# ProProject_PowerDistribution_1_1.net
KiCad netlist of a schematic drawn in EasyEDA Pro
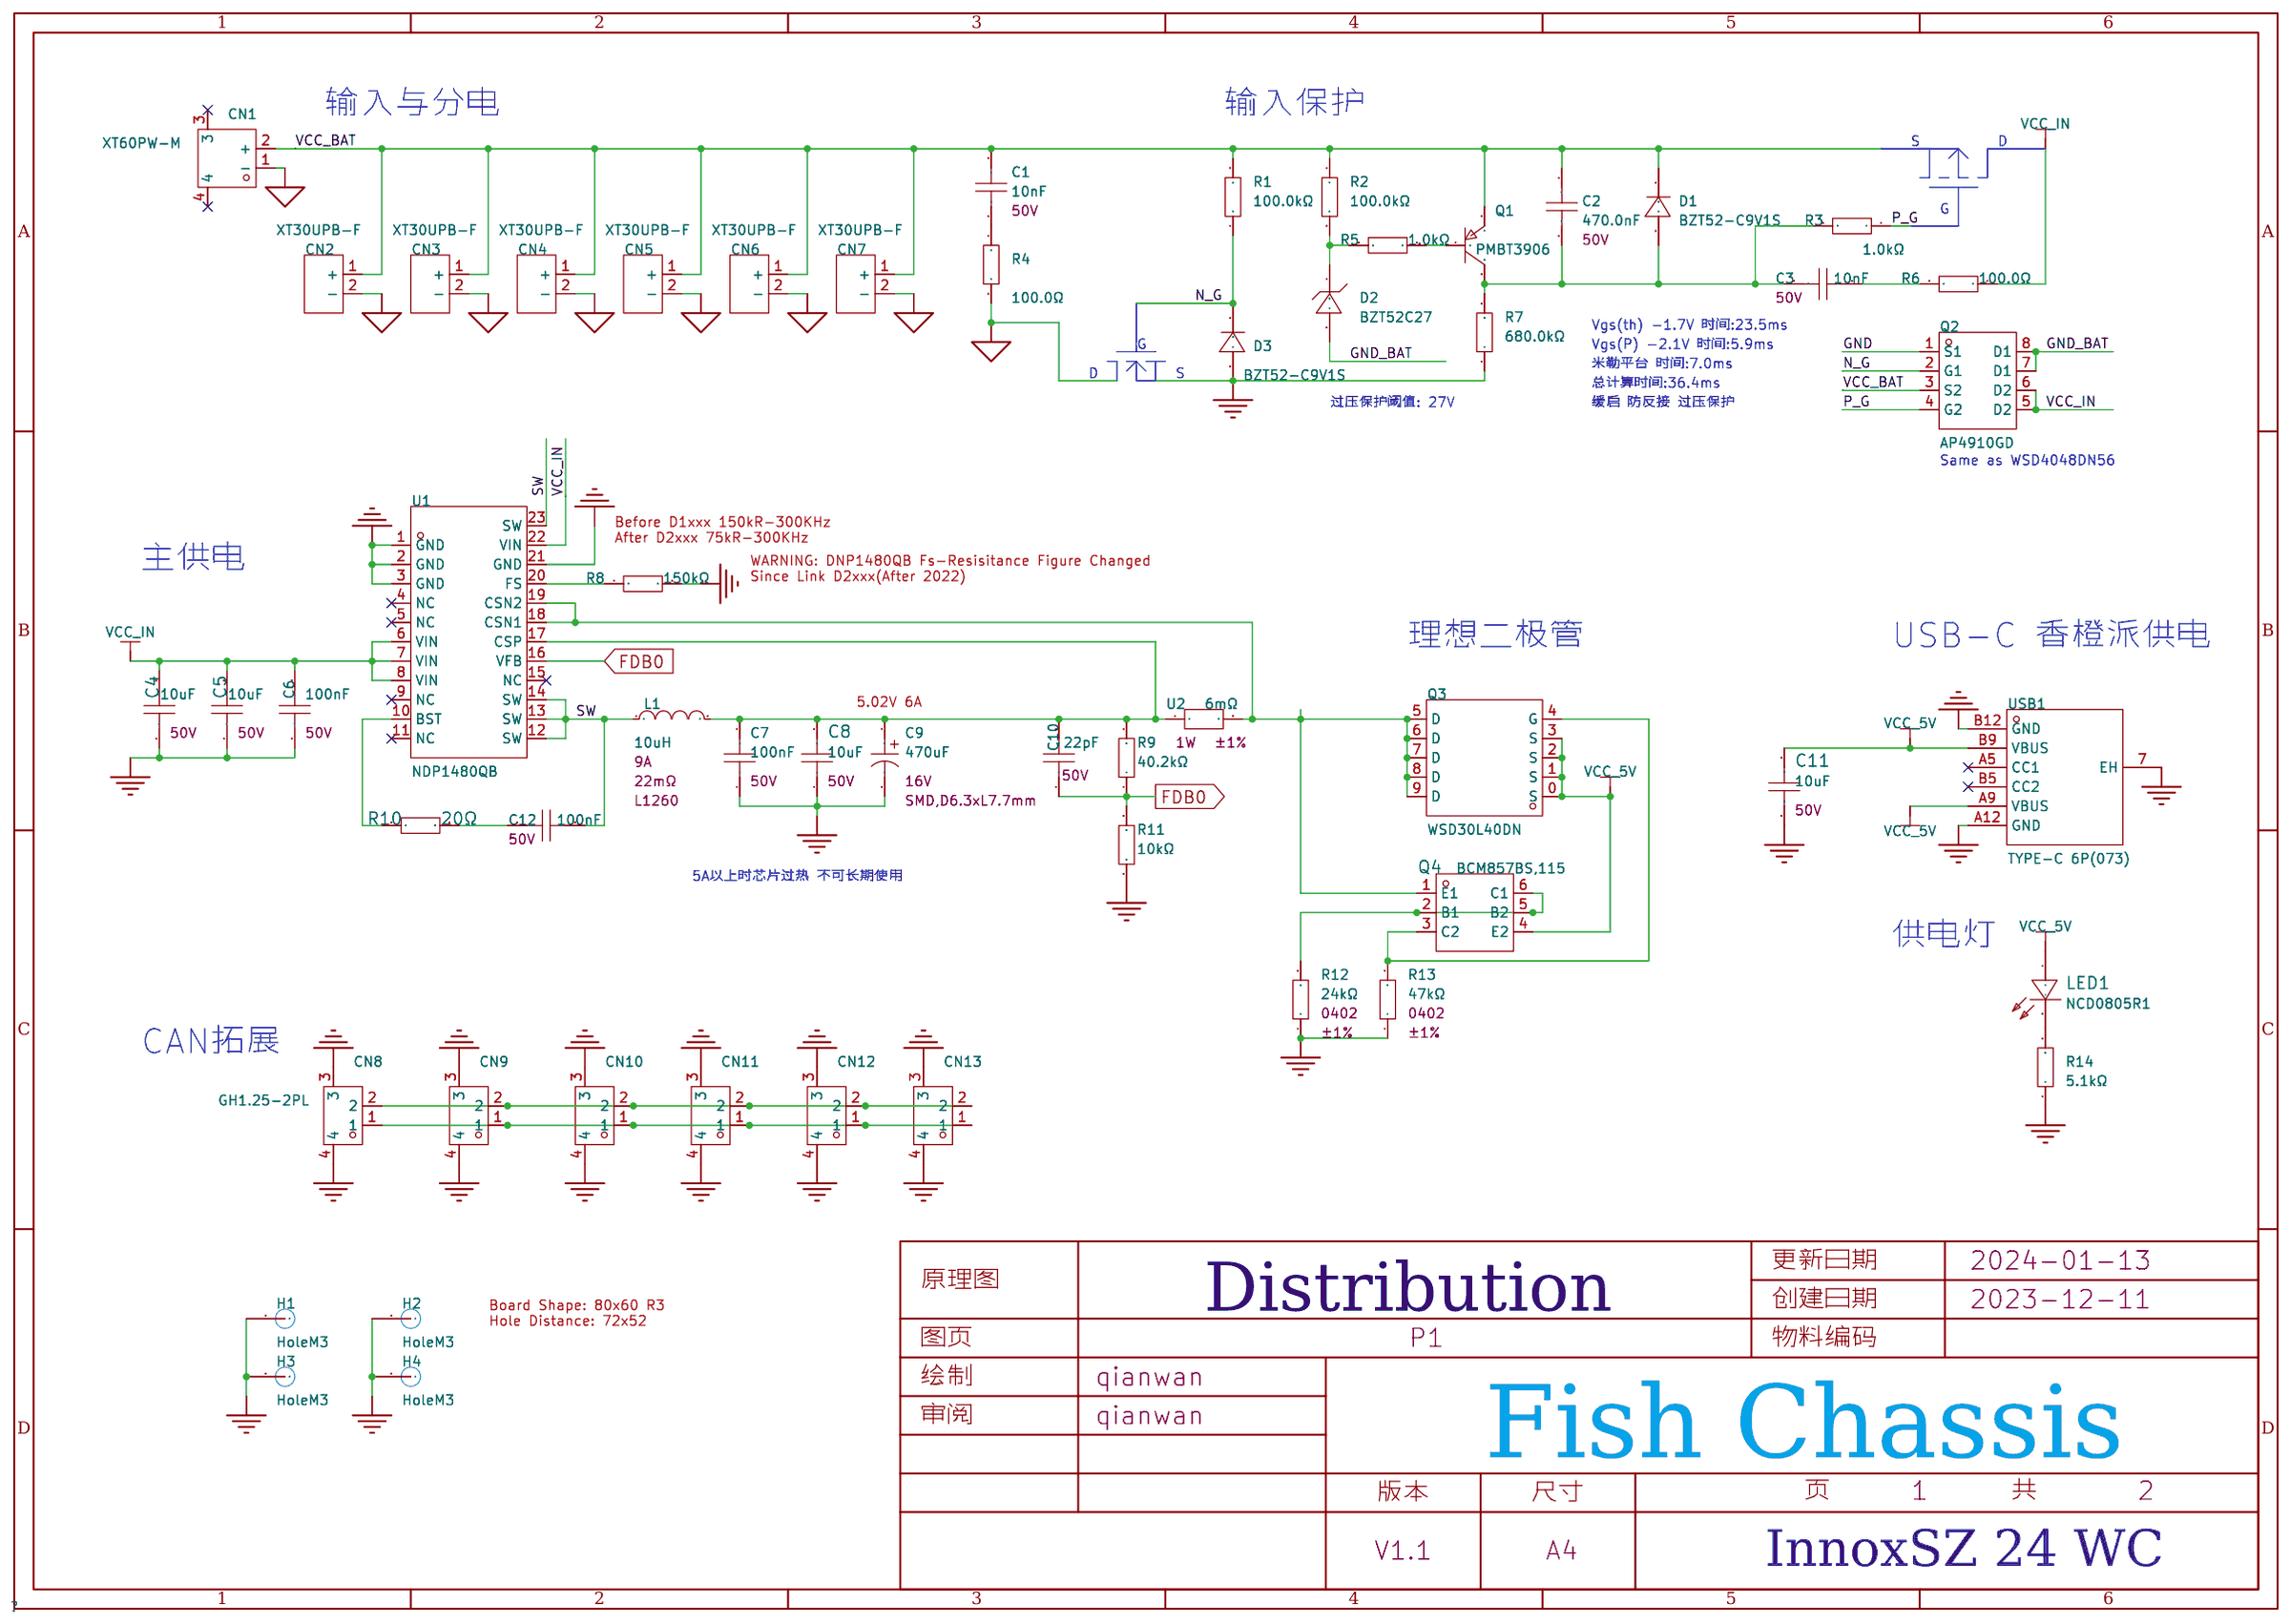
[diagram p0: P1]
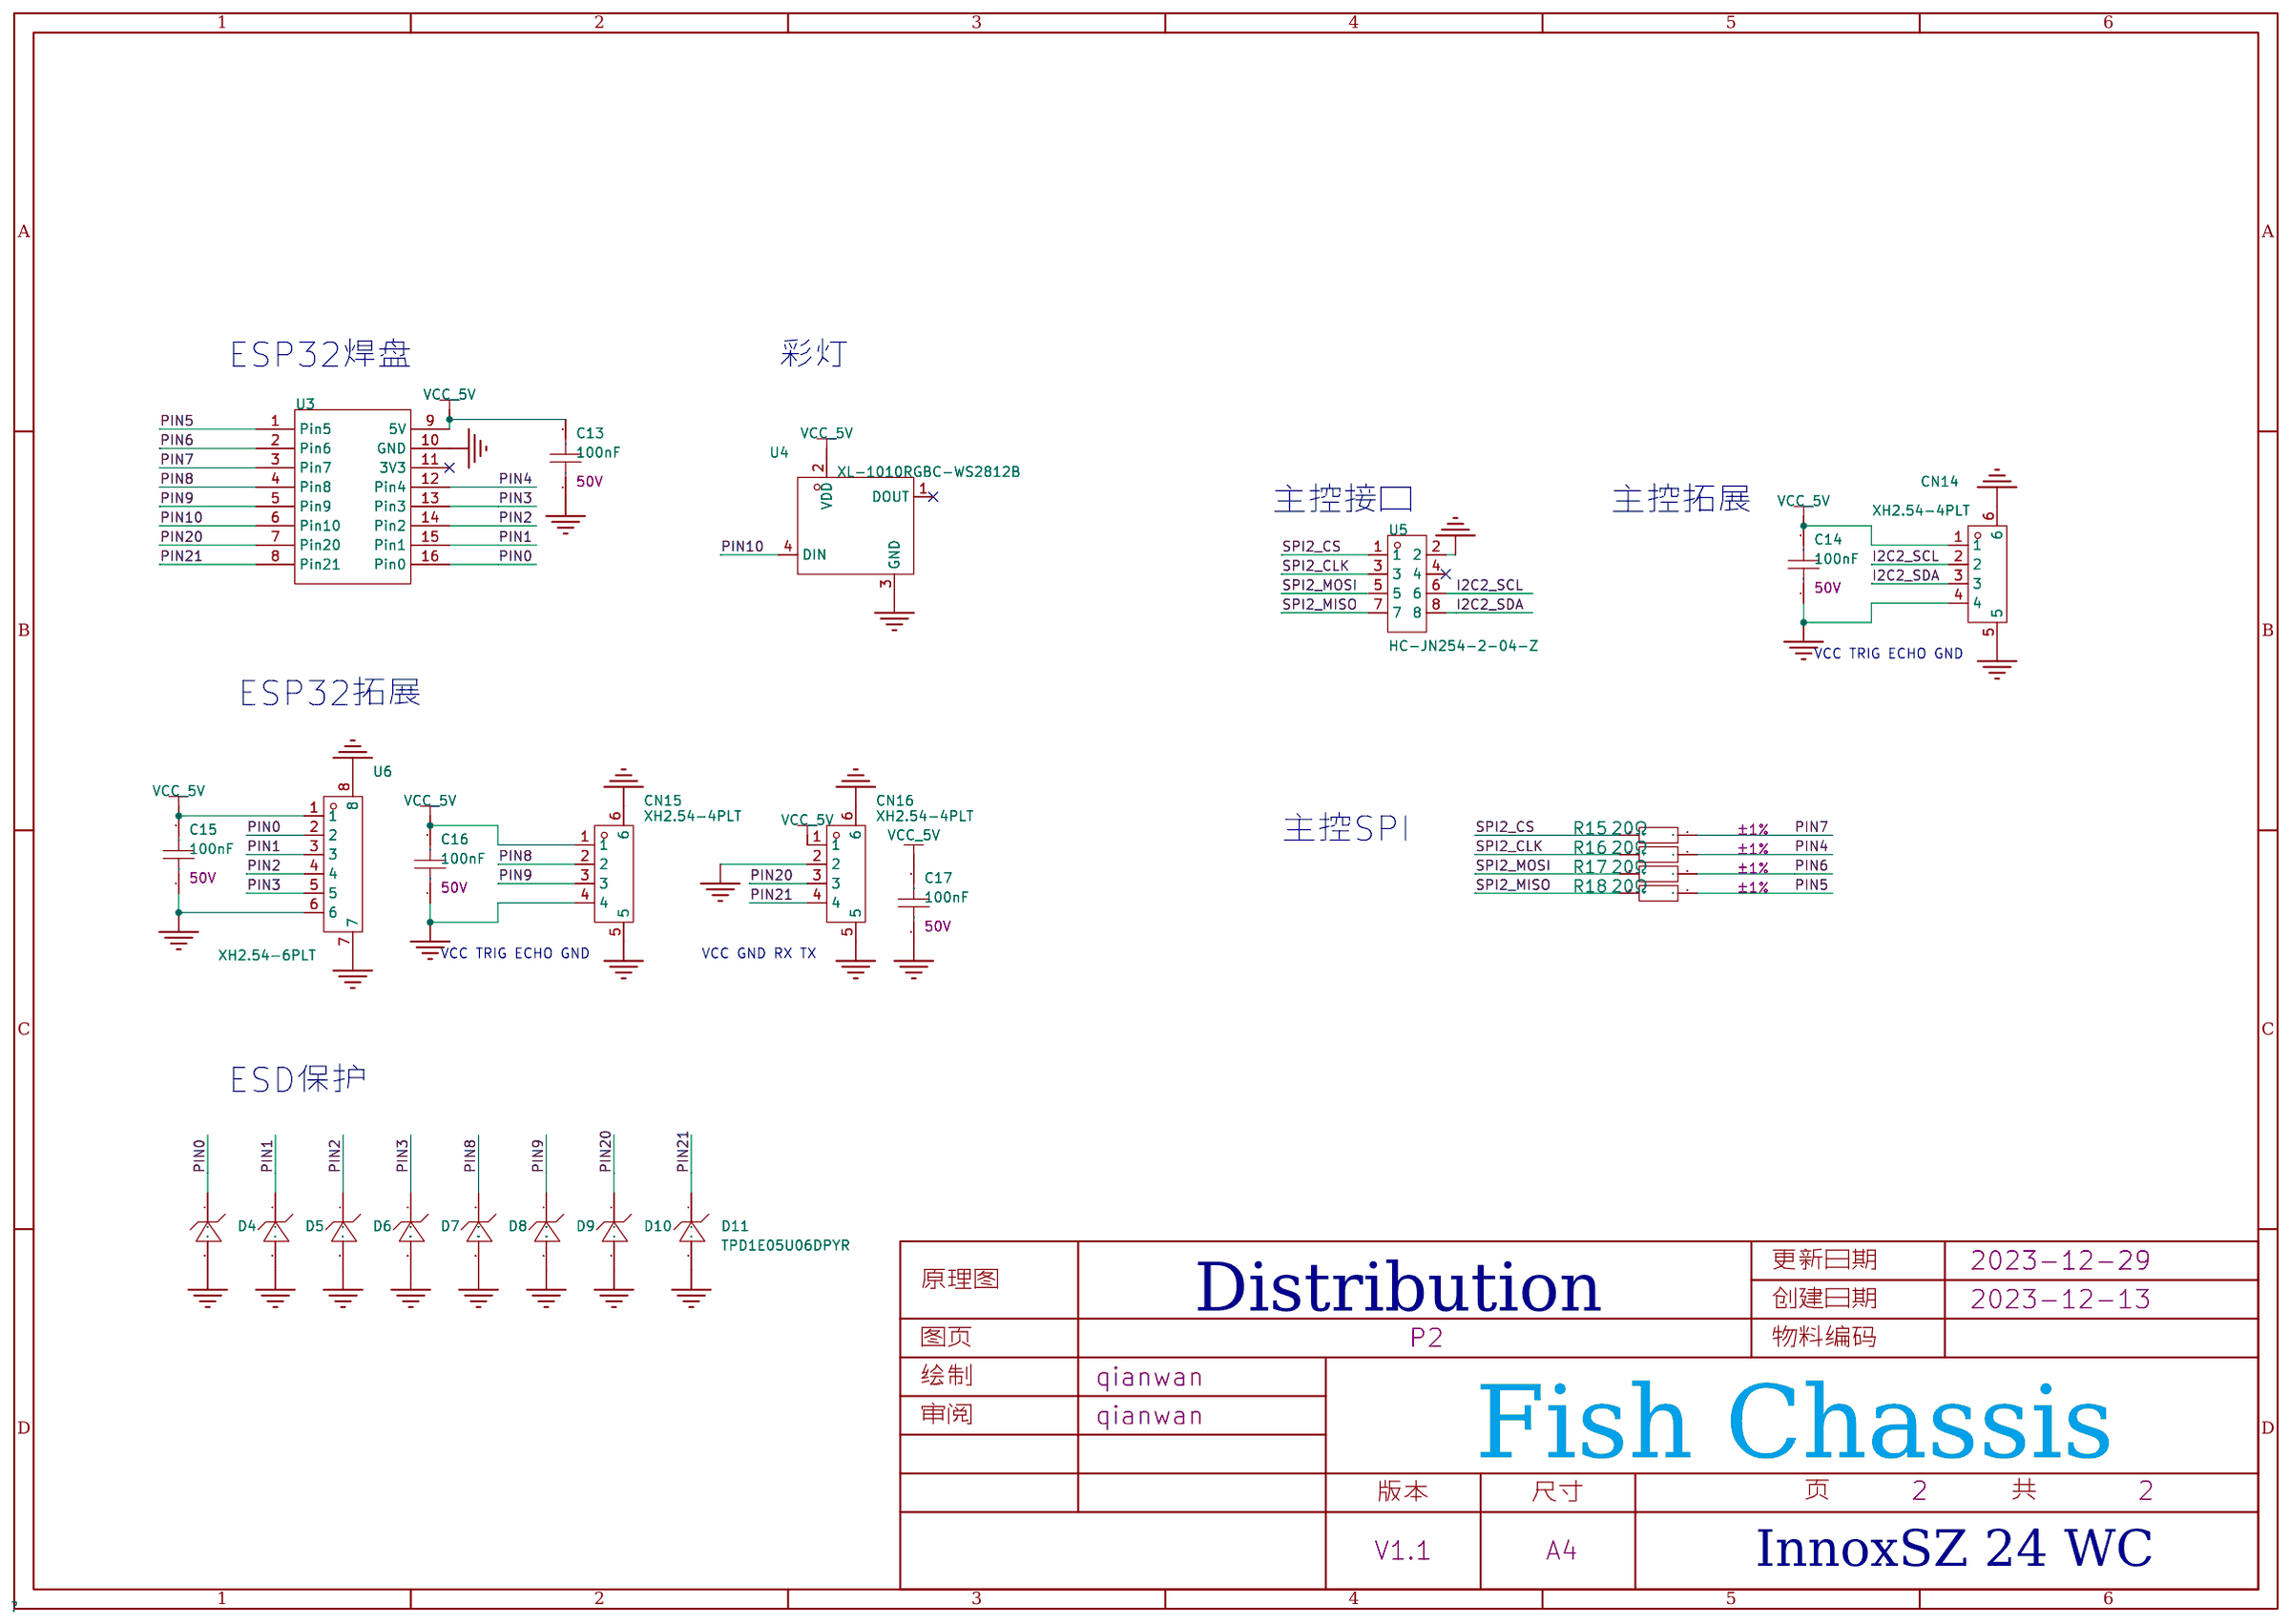
[diagram p1: P2]

(export (version "E")
  (design (tool "Eeschema 10.0.6"))
  (components
    (comp (ref "C1")
      (value "10nF")
      (footprint "easyedapro:C0402")
      (description "容值:10nF;精度:±10%;额定电压:50V;材质(温度系数):X7R;")
      (fields
        (field (name "Manufacturer Part") "GCM155R71H103KA55D")
        (field (name "Manufacturer") "muRata(村田)")
        (field (name "Voltage Rated") "50V")
      )
      (libsource (lib "easyedapro") (part "GCM155R71H103KA55D"))
    )
    (comp (ref "C2")
      (value "470.0nF")
      (footprint "easyedapro:C0402")
      (description "容值:10nF;精度:±10%;额定电压:25V;材质(温度系数):X7R;")
      (fields
        (field (name "Manufacturer Part") "CC0402KRX7R8BB103")
        (field (name "Manufacturer") "YAGEO(国巨)")
        (field (name "Voltage Rated") "50V")
      )
      (libsource (lib "easyedapro") (part "CC0402KRX7R8BB103"))
    )
    (comp (ref "C3")
      (value "10nF")
      (footprint "easyedapro:C0402")
      (description "容值:10nF;精度:±10%;额定电压:50V;材质(温度系数):X7R;")
      (fields
        (field (name "Manufacturer Part") "GCM155R71H103KA55D")
        (field (name "Manufacturer") "muRata(村田)")
        (field (name "Voltage Rated") "50V")
      )
      (libsource (lib "easyedapro") (part "GCM155R71H103KA55D"))
    )
    (comp (ref "C4")
      (value "10uF")
      (footprint "easyedapro:C1206")
      (description "容值:10uF;精度:±10%;额定电压:50V;材质(温度系数):X5R;")
      (fields
        (field (name "Manufacturer Part") "GRM31CR61H106KA12L")
        (field (name "Manufacturer") "muRata(村田)")
        (field (name "Voltage Rated") "50V")
      )
      (libsource (lib "easyedapro") (part "GRM31CR61H106KA12L"))
    )
    (comp (ref "C5")
      (value "10uF")
      (footprint "easyedapro:C1206")
      (description "容值:10uF;精度:±10%;额定电压:50V;材质(温度系数):X5R;")
      (fields
        (field (name "Manufacturer Part") "GRM31CR61H106KA12L")
        (field (name "Manufacturer") "muRata(村田)")
        (field (name "Voltage Rated") "50V")
      )
      (libsource (lib "easyedapro") (part "GRM31CR61H106KA12L"))
    )
    (comp (ref "C6")
      (value "100nF")
      (footprint "easyedapro:C0402")
      (description "容值:100nF;精度:±10%;额定电压:50V;材质(温度系数):X7R;")
      (fields
        (field (name "Manufacturer Part") "CL05B104KB54PNC")
        (field (name "Manufacturer") "SAMSUNG(三星)")
        (field (name "Voltage Rated") "50V")
      )
      (libsource (lib "easyedapro") (part "CL05B104KB54PNC"))
    )
    (comp (ref "C7")
      (value "100nF")
      (footprint "easyedapro:C0402")
      (description "容值:100nF;精度:±10%;额定电压:50V;材质(温度系数):X7R;")
      (fields
        (field (name "Manufacturer Part") "CL05B104KB54PNC")
        (field (name "Manufacturer") "SAMSUNG(三星)")
        (field (name "Voltage Rated") "50V")
      )
      (libsource (lib "easyedapro") (part "CL05B104KB54PNC"))
    )
    (comp (ref "C8")
      (value "10uF")
      (footprint "easyedapro:C1206")
      (description "容值:10uF;精度:±10%;额定电压:50V;材质(温度系数):X5R;")
      (fields
        (field (name "Manufacturer Part") "GRM31CR61H106KA12L")
        (field (name "Manufacturer") "muRata(村田)")
        (field (name "Voltage Rated") "50V")
      )
      (libsource (lib "easyedapro") (part "GRM31CR61H106KA12L"))
    )
    (comp (ref "C9")
      (value "470uF")
      (footprint "easyedapro:CAP-SMD_BD6.3-L6.6-W6.6-LS7.6-RD")
      (description "容值:470uF;精度:±20%;额定电压:16V;纹波电流:185mA@120Hz;")
      (fields
        (field (name "Manufacturer Part") "RVT1C471M0607")
        (field (name "Manufacturer") "ROQANG(容强)")
        (field (name "Rated Voltage") "16V")
        (field (name "Supplier Footprint") "SMD,D6.3xL7.7mm")
      )
      (libsource (lib "easyedapro") (part "RVT1C471M0607"))
    )
    (comp (ref "C10")
      (value "22pF")
      (footprint "easyedapro:C0402")
      (description "容值:22pF;精度:±5%;额定电压:50V;材质(温度系数):C0G;")
      (fields
        (field (name "Manufacturer Part") "GRM1555C1H220JA01D")
        (field (name "Manufacturer") "muRata(村田)")
        (field (name "Voltage Rated") "50V")
      )
      (libsource (lib "easyedapro") (part "GRM1555C1H220JA01D"))
    )
    (comp (ref "C11")
      (value "10uF")
      (footprint "easyedapro:C1206")
      (description "容值:10uF;精度:±10%;额定电压:50V;材质(温度系数):X5R;")
      (fields
        (field (name "Manufacturer Part") "GRM31CR61H106KA12L")
        (field (name "Manufacturer") "muRata(村田)")
        (field (name "Voltage Rated") "50V")
      )
      (libsource (lib "easyedapro") (part "GRM31CR61H106KA12L"))
    )
    (comp (ref "C12")
      (value "100nF")
      (footprint "easyedapro:C0402")
      (description "容值:100nF;精度:±10%;额定电压:50V;材质(温度系数):X7R;")
      (fields
        (field (name "Manufacturer Part") "CL05B104KB54PNC")
        (field (name "Manufacturer") "SAMSUNG(三星)")
        (field (name "Voltage Rated") "50V")
      )
      (libsource (lib "easyedapro") (part "CL05B104KB54PNC"))
    )
    (comp (ref "CN1")
      (value "XT60PW-M")
      (footprint "easyedapro:CONN-TH_XT60PW-M")
      (description "类别:-;类型1:-;")
      (fields (field (name "Manufacturer") "AMASS(艾迈斯)"))
      (libsource (lib "easyedapro") (part "XT60PW-M"))
    )
    (comp (ref "CN2")
      (value "XT30UPB-F")
      (footprint "easyedapro:CONN-TH_XT30UPB-F")
      (description "类别:-;类型1:-;")
      (fields (field (name "Manufacturer Part") "XT30UPB-F30.G.Y") (field (name "Manufacturer") "AMASS(艾迈斯)"))
      (libsource (lib "easyedapro") (part "XT30UPB-F"))
    )
    (comp (ref "CN3")
      (value "XT30UPB-F")
      (footprint "easyedapro:CONN-TH_XT30UPB-F")
      (description "类别:-;类型1:-;")
      (fields (field (name "Manufacturer Part") "XT30UPB-F30.G.Y") (field (name "Manufacturer") "AMASS(艾迈斯)"))
      (libsource (lib "easyedapro") (part "XT30UPB-F"))
    )
    (comp (ref "CN4")
      (value "XT30UPB-F")
      (footprint "easyedapro:CONN-TH_XT30UPB-F")
      (description "类别:-;类型1:-;")
      (fields (field (name "Manufacturer Part") "XT30UPB-F30.G.Y") (field (name "Manufacturer") "AMASS(艾迈斯)"))
      (libsource (lib "easyedapro") (part "XT30UPB-F"))
    )
    (comp (ref "CN5")
      (value "XT30UPB-F")
      (footprint "easyedapro:CONN-TH_XT30UPB-F")
      (description "类别:-;类型1:-;")
      (fields (field (name "Manufacturer Part") "XT30UPB-F30.G.Y") (field (name "Manufacturer") "AMASS(艾迈斯)"))
      (libsource (lib "easyedapro") (part "XT30UPB-F"))
    )
    (comp (ref "CN6")
      (value "XT30UPB-F")
      (footprint "easyedapro:CONN-TH_XT30UPB-F")
      (description "类别:-;类型1:-;")
      (fields (field (name "Manufacturer Part") "XT30UPB-F30.G.Y") (field (name "Manufacturer") "AMASS(艾迈斯)"))
      (libsource (lib "easyedapro") (part "XT30UPB-F"))
    )
    (comp (ref "CN7")
      (value "XT30UPB-F")
      (footprint "easyedapro:CONN-TH_XT30UPB-F")
      (description "类别:-;类型1:-;")
      (fields (field (name "Manufacturer Part") "XT30UPB-F30.G.Y") (field (name "Manufacturer") "AMASS(艾迈斯)"))
      (libsource (lib "easyedapro") (part "XT30UPB-F"))
    )
    (comp (ref "CN8")
      (value "GH1.25-2PL")
      (footprint "easyedapro:CONN-SMD_2P-P1.25_L125WVS-02PS")
      (description "插针结构:1x2P;间距:1.25mm;安装方式:立贴;总PIN数:2P;排数:1;每排PIN数:2;额定电流:1A;工作温度范围:-40°C~+110°C;")
      (fields (field (name "Manufacturer Part") "L125WVS-02PS") (field (name "Manufacturer") "DEALON(德艺隆)"))
      (libsource (lib "easyedapro") (part "L125WVS-02PS"))
    )
    (comp (ref "CN9")
      (value "L125WVS-02PS")
      (footprint "easyedapro:CONN-SMD_2P-P1.25_L125WVS-02PS")
      (description "插针结构:1x2P;间距:1.25mm;安装方式:立贴;总PIN数:2P;排数:1;每排PIN数:2;额定电流:1A;工作温度范围:-40°C~+110°C;")
      (fields (field (name "Manufacturer") "DEALON(德艺隆)"))
      (libsource (lib "easyedapro") (part "L125WVS-02PS"))
    )
    (comp (ref "CN10")
      (value "L125WVS-02PS")
      (footprint "easyedapro:CONN-SMD_2P-P1.25_L125WVS-02PS")
      (description "插针结构:1x2P;间距:1.25mm;安装方式:立贴;总PIN数:2P;排数:1;每排PIN数:2;额定电流:1A;工作温度范围:-40°C~+110°C;")
      (fields (field (name "Manufacturer") "DEALON(德艺隆)"))
      (libsource (lib "easyedapro") (part "L125WVS-02PS"))
    )
    (comp (ref "CN11")
      (value "L125WVS-02PS")
      (footprint "easyedapro:CONN-SMD_2P-P1.25_L125WVS-02PS")
      (description "插针结构:1x2P;间距:1.25mm;安装方式:立贴;总PIN数:2P;排数:1;每排PIN数:2;额定电流:1A;工作温度范围:-40°C~+110°C;")
      (fields (field (name "Manufacturer") "DEALON(德艺隆)"))
      (libsource (lib "easyedapro") (part "L125WVS-02PS"))
    )
    (comp (ref "CN12")
      (value "L125WVS-02PS")
      (footprint "easyedapro:CONN-SMD_2P-P1.25_L125WVS-02PS")
      (description "插针结构:1x2P;间距:1.25mm;安装方式:立贴;总PIN数:2P;排数:1;每排PIN数:2;额定电流:1A;工作温度范围:-40°C~+110°C;")
      (fields (field (name "Manufacturer") "DEALON(德艺隆)"))
      (libsource (lib "easyedapro") (part "L125WVS-02PS"))
    )
    (comp (ref "CN13")
      (value "L125WVS-02PS")
      (footprint "easyedapro:CONN-SMD_2P-P1.25_L125WVS-02PS")
      (description "插针结构:1x2P;间距:1.25mm;安装方式:立贴;总PIN数:2P;排数:1;每排PIN数:2;额定电流:1A;工作温度范围:-40°C~+110°C;")
      (fields (field (name "Manufacturer") "DEALON(德艺隆)"))
      (libsource (lib "easyedapro") (part "L125WVS-02PS"))
    )
    (comp (ref "D1")
      (value "BZT52-C9V1S")
      (footprint "easyedapro:SOD-323_L1.8-W1.3-LS2.5-RD")
      (description "二极管配置:独立式;稳压值(标称值):9.1V;稳压值(范围):8.65V~9.56V;精度:-;功率:200mW;反向电流(Ir):100nA@7V;阻抗(Zzt):10Ω;")
      (fields
        (field (name "Manufacturer Part") "BZT52-C9V1S_R1_00001")
        (field (name "Manufacturer") "PANJIT(强茂)")
      )
      (libsource (lib "easyedapro") (part "BZT52_C9V1S_R1_00001"))
    )
    (comp (ref "D2")
      (value "BZT52C27")
      (footprint "easyedapro:SOD-123_L2.7-W1.6-LS3.7-RD")
      (description "二极管配置:独立式;稳压值(标称值):27V;稳压值(范围):25.1V~28.9V;精度:-;功率:350mW;反向电流(Ir):100nA@18.9V;阻抗(Zzt):80Ω;")
      (fields (field (name "Manufacturer") "CJ(江苏长电/长晶)"))
      (libsource (lib "easyedapro") (part "BZT52C27"))
    )
    (comp (ref "D3")
      (value "BZT52-C9V1S")
      (footprint "easyedapro:SOD-323_L1.8-W1.3-LS2.5-RD")
      (description "二极管配置:独立式;稳压值(标称值):9.1V;稳压值(范围):8.65V~9.56V;精度:-;功率:200mW;反向电流(Ir):100nA@7V;阻抗(Zzt):10Ω;")
      (fields
        (field (name "Manufacturer Part") "BZT52-C9V1S_R1_00001")
        (field (name "Manufacturer") "PANJIT(强茂)")
      )
      (libsource (lib "easyedapro") (part "BZT52_C9V1S_R1_00001"))
    )
    (comp (ref "H1")
      (value "HoleM3")
      (footprint "easyedapro:M3孔")
      (description "M3孔")
      (libsource (lib "easyedapro") (part "M3孔"))
    )
    (comp (ref "H2")
      (value "HoleM3")
      (footprint "easyedapro:M3孔")
      (description "M3孔")
      (libsource (lib "easyedapro") (part "M3孔"))
    )
    (comp (ref "H3")
      (value "HoleM3")
      (footprint "easyedapro:M3孔")
      (description "M3孔")
      (libsource (lib "easyedapro") (part "M3孔"))
    )
    (comp (ref "H4")
      (value "HoleM3")
      (footprint "easyedapro:M3孔")
      (description "M3孔")
      (libsource (lib "easyedapro") (part "M3孔"))
    )
    (comp (ref "L1")
      (value "10uH")
      (footprint "easyedapro:IND-SMD_L13.5-W12.8_TMPC1265HP")
      (description "类型:-;电感值:10uH;精度:±20%;额定电流:9A;饱和电流(Isat):12A;")
      (fields
        (field (name "Manufacturer Part") "MWSA1205S-100MT")
        (field (name "Manufacturer") "Sunlord(顺络)")
        (field (name "DC Resistance (DCR)") "22mΩ")
        (field (name "Rated Current") "9A")
        (field (name "其他描述") "L1260")
      )
      (libsource (lib "easyedapro") (part "MWSA1205S-100MT"))
    )
    (comp (ref "LED1")
      (value "NCD0805R1")
      (footprint "easyedapro:LED0805-R-RD")
      (description "发光颜色:红灯;")
      (fields (field (name "Manufacturer") "国星光电"))
      (libsource (lib "easyedapro") (part "FC-2012HRK-620D"))
    )
    (comp (ref "Q1")
      (value "PMBT3906")
      (footprint "easyedapro:SOT-23-3_L2.9-W1.3-P1.90-LS2.4-BR")
      (description "晶体管类型:PNP;集射极击穿电压(Vceo):40V;集电极电流(Ic):200mA;功率(Pd):250mW;直流电流增益(hFE@Ic,Vce):100@10mA,1V;")
      (fields (field (name "Manufacturer Part") "PMBT3906,215") (field (name "Manufacturer") "Nexperia(安世)"))
      (libsource (lib "easyedapro") (part "PMBT3906,215"))
    )
    (comp (ref "Q2")
      (value "AP4910GD")
      (footprint "easyedapro:DFN-8_L5.8-W4.9-P1.27-LS6.0-BL")
      (description "类型:1个N沟道和1个P沟道;连续漏极电流(Id):-;功率(Pd):-;导通电阻(RDS(on)@Vgs,Id):-;阈值电压(Vgs(th)@Id):-;")
      (fields (field (name "Manufacturer") "ALLPOWER(铨力)"))
      (libsource (lib "easyedapro") (part "AP4910GD"))
    )
    (comp (ref "Q3")
      (value "WSD30L40DN")
      (footprint "easyedapro:DFN-8_L3.0-W3.0-P0.65-BL-A")
      (description "类型:P沟道;漏源电压(Vdss):30V;连续漏极电流(Id):40A;功率(Pd):32.9W;导通电阻(RDS(on)@Vgs,Id):14mΩ@10V,20A;")
      (fields (field (name "Manufacturer") "WINSOK(微硕)"))
      (libsource (lib "easyedapro") (part "WSD30L40DN"))
    )
    (comp (ref "Q4")
      (value "BCM857BS,115")
      (footprint "easyedapro:SOT-363_L2.0-W1.3-P0.65-LS2.1-BL")
      (description "晶体管类型:2个PNP配对;集射极击穿电压(Vceo):45V;集电极电流(Ic):100mA;功率(Pd):300mW;直流电流增益(hFE@Ic,Vce):200@2mA,5V;")
      (fields (field (name "Manufacturer") "Nexperia(安世)"))
      (libsource (lib "easyedapro") (part "BCM857BS,115"))
    )
    (comp (ref "R1")
      (value "100.0kΩ")
      (footprint "easyedapro:R0402")
      (description "电阻类型:厚膜电阻;阻值:100kΩ;精度:±1%;功率:62.5mW;")
      (fields (field (name "Manufacturer Part") "RC0402FR-07100KL") (field (name "Manufacturer") "YAGEO(国巨)"))
      (libsource (lib "easyedapro") (part "RC0402FR-07100KL"))
    )
    (comp (ref "R2")
      (value "100.0kΩ")
      (footprint "easyedapro:R0402")
      (description "电阻类型:厚膜电阻;阻值:100kΩ;精度:±1%;功率:62.5mW;")
      (fields (field (name "Manufacturer Part") "RC0402FR-07100KL") (field (name "Manufacturer") "YAGEO(国巨)"))
      (libsource (lib "easyedapro") (part "RC0402FR-07100KL"))
    )
    (comp (ref "R3")
      (value "1.0kΩ")
      (footprint "easyedapro:R0402")
      (description "电阻类型:厚膜电阻;阻值:100kΩ;精度:±1%;功率:62.5mW;")
      (fields (field (name "Manufacturer Part") "RC0402FR-07100KL") (field (name "Manufacturer") "YAGEO(国巨)"))
      (libsource (lib "easyedapro") (part "RC0402FR-07100KL"))
    )
    (comp (ref "R4")
      (value "100.0Ω")
      (footprint "easyedapro:R0402")
      (description "电阻类型:厚膜电阻;阻值:100kΩ;精度:±1%;功率:62.5mW;")
      (fields (field (name "Manufacturer Part") "RC0402FR-07100KL") (field (name "Manufacturer") "YAGEO(国巨)"))
      (libsource (lib "easyedapro") (part "RC0402FR-07100KL"))
    )
    (comp (ref "R5")
      (value "1.0kΩ")
      (footprint "easyedapro:R0402")
      (description "电阻类型:厚膜电阻;阻值:100kΩ;精度:±1%;功率:62.5mW;")
      (fields (field (name "Manufacturer Part") "RC0402FR-07100KL") (field (name "Manufacturer") "YAGEO(国巨)"))
      (libsource (lib "easyedapro") (part "RC0402FR-07100KL"))
    )
    (comp (ref "R6")
      (value "100.0Ω")
      (footprint "easyedapro:R0402")
      (description "电阻类型:厚膜电阻;阻值:100kΩ;精度:±1%;功率:62.5mW;")
      (fields (field (name "Manufacturer Part") "RC0402FR-07100KL") (field (name "Manufacturer") "YAGEO(国巨)"))
      (libsource (lib "easyedapro") (part "RC0402FR-07100KL"))
    )
    (comp (ref "R7")
      (value "680.0kΩ")
      (footprint "easyedapro:R0402")
      (description "电阻类型:厚膜电阻;阻值:100kΩ;精度:±1%;功率:62.5mW;")
      (fields (field (name "Manufacturer Part") "RC0402FR-07100KL") (field (name "Manufacturer") "YAGEO(国巨)"))
      (libsource (lib "easyedapro") (part "RC0402FR-07100KL"))
    )
    (comp (ref "R8")
      (value "150kΩ")
      (footprint "easyedapro:R0402")
      (description "电阻类型:厚膜电阻;阻值:150kΩ;精度:±1%;功率:62.5mW;")
      (fields
        (field (name "Manufacturer Part") "0402WGF1503TCE")
        (field (name "Manufacturer") "UNI-ROYAL(厚声)")
      )
      (libsource (lib "easyedapro") (part "0402WGF1503TCE"))
    )
    (comp (ref "R9")
      (value "40.2kΩ")
      (footprint "easyedapro:R0402")
      (description "电阻类型:厚膜电阻;阻值:40.2kΩ;精度:±1%;功率:62.5mW;")
      (fields
        (field (name "Manufacturer Part") "0402WGF4022TCE")
        (field (name "Manufacturer") "UNI-ROYAL(厚声)")
      )
      (libsource (lib "easyedapro") (part "0402WGF4022TCE"))
    )
    (comp (ref "R10")
      (value "20Ω")
      (footprint "easyedapro:R0402")
      (description "电阻类型:厚膜电阻;阻值:22Ω;精度:±1%;功率:62.5mW;温度系数:±100ppm/°C;")
      (fields
        (field (name "Manufacturer Part") "0402WGF200JTCE")
        (field (name "Manufacturer") "UNI-ROYAL(厚声)")
      )
      (libsource (lib "easyedapro") (part "0402WGF220JTCE"))
    )
    (comp (ref "R11")
      (value "10kΩ")
      (footprint "easyedapro:R0402")
      (description "电阻类型:厚膜电阻;阻值:10kΩ;精度:±1%;功率:62.5mW;")
      (fields (field (name "Manufacturer Part") "RC0402FR-0710KL") (field (name "Manufacturer") "YAGEO(国巨)"))
      (libsource (lib "easyedapro") (part "RC0402FR-0710KL"))
    )
    (comp (ref "R12")
      (value "24kΩ")
      (footprint "easyedapro:R0402")
      (description "电阻类型:厚膜电阻;阻值:24kΩ;精度:±1%;功率:62.5mW;温度系数:±100ppm/°C;")
      (fields
        (field (name "Manufacturer Part") "0402WGF2402TCE")
        (field (name "Manufacturer") "UNI-ROYAL(厚声)")
        (field (name "Supplier Footprint") "0402")
        (field (name "Tolerance") "±1%")
      )
      (libsource (lib "easyedapro") (part "0402WGF2402TCE"))
    )
    (comp (ref "R13")
      (value "47kΩ")
      (footprint "easyedapro:R0402")
      (description "电阻类型:厚膜电阻;阻值:47kΩ;精度:±1%;功率:62.5mW;温度系数:±100ppm/°C;")
      (fields
        (field (name "Manufacturer Part") "0402WGF4702TCE")
        (field (name "Manufacturer") "UNI-ROYAL(厚声)")
        (field (name "Supplier Footprint") "0402")
        (field (name "Tolerance") "±1%")
      )
      (libsource (lib "easyedapro") (part "0402WGF4702TCE"))
    )
    (comp (ref "R14")
      (value "5.1kΩ")
      (footprint "easyedapro:R0402")
      (description "电阻类型:厚膜电阻;阻值:10kΩ;精度:±1%;功率:62.5mW;")
      (fields (field (name "Manufacturer Part") "RC0402FR-0710KL") (field (name "Manufacturer") "YAGEO(国巨)"))
      (libsource (lib "easyedapro") (part "RC0402FR-0710KL"))
    )
    (comp (ref "U1")
      (value "NDP1480QB")
      (footprint "easyedapro:QFN-20_L5.0-W5.0-P0.80-TL-NDP1460QB")
      (fields (field (name "Manufacturer") "NDP(芯潭微)"))
      (libsource (lib "easyedapro") (part "NDP1480QB_Correct"))
    )
    (comp (ref "U2")
      (value "6mΩ")
      (footprint "easyedapro:R1206")
      (description "阻值:6mΩ;精度:±1%;功率:1W;温度系数:±100ppm/°C;")
      (fields
        (field (name "Manufacturer Part") "PA1206FRF470R006L")
        (field (name "Manufacturer") "YAGEO(国巨)")
        (field (name "Power(Watts)") "1W")
        (field (name "Tolerance") "±1%")
      )
      (libsource (lib "easyedapro") (part "PA1206FRF470R006L"))
    )
    (comp (ref "USB1")
      (value "TYPE-C 6P(073)")
      (footprint "easyedapro:TYPE-C-SMD_TYPE-C-6P")
      (description "连接器类型:Type-C;标准:-;公母:母;触点数量:6P;端口数量:1;安装方式:卧贴;额定电流 - 电源:5A;工作温度范围:-25°C~+85°C;")
      (fields (field (name "Manufacturer") "SHOU HAN(首韩)"))
      (libsource (lib "easyedapro") (part "TYPE-C 6P(073)"))
    )
    (comp (ref "C13")
      (value "100nF")
      (footprint "easyedapro:C0402")
      (description "容值:100nF;精度:±10%;额定电压:50V;材质(温度系数):X7R;")
      (fields
        (field (name "Manufacturer Part") "CL05B104KB54PNC")
        (field (name "Manufacturer") "SAMSUNG(三星)")
        (field (name "Voltage Rated") "50V")
      )
      (libsource (lib "easyedapro") (part "CL05B104KB54PNC"))
    )
    (comp (ref "C14")
      (value "100nF")
      (footprint "easyedapro:C0402")
      (description "容值:100nF;精度:±10%;额定电压:50V;材质(温度系数):X7R;")
      (fields
        (field (name "Manufacturer Part") "CL05B104KB54PNC")
        (field (name "Manufacturer") "SAMSUNG(三星)")
        (field (name "Voltage Rated") "50V")
      )
      (libsource (lib "easyedapro") (part "CL05B104KB54PNC"))
    )
    (comp (ref "C15")
      (value "100nF")
      (footprint "easyedapro:C0402")
      (description "容值:100nF;精度:±10%;额定电压:50V;材质(温度系数):X7R;")
      (fields
        (field (name "Manufacturer Part") "CL05B104KB54PNC")
        (field (name "Manufacturer") "SAMSUNG(三星)")
        (field (name "Voltage Rated") "50V")
      )
      (libsource (lib "easyedapro") (part "CL05B104KB54PNC"))
    )
    (comp (ref "C16")
      (value "100nF")
      (footprint "easyedapro:C0402")
      (description "容值:100nF;精度:±10%;额定电压:50V;材质(温度系数):X7R;")
      (fields
        (field (name "Manufacturer Part") "CL05B104KB54PNC")
        (field (name "Manufacturer") "SAMSUNG(三星)")
        (field (name "Voltage Rated") "50V")
      )
      (libsource (lib "easyedapro") (part "CL05B104KB54PNC"))
    )
    (comp (ref "C17")
      (value "100nF")
      (footprint "easyedapro:C0402")
      (description "容值:100nF;精度:±10%;额定电压:50V;材质(温度系数):X7R;")
      (fields
        (field (name "Manufacturer Part") "CL05B104KB54PNC")
        (field (name "Manufacturer") "SAMSUNG(三星)")
        (field (name "Voltage Rated") "50V")
      )
      (libsource (lib "easyedapro") (part "CL05B104KB54PNC"))
    )
    (comp (ref "CN14")
      (value "XH2.54-4PLT")
      (footprint "easyedapro:CONN-SMD_4P-P2.50_XUNPU_WAFER-XH2.54-4PLB")
      (description "插针结构:1x4P;间距:2.5mm;安装方式:立贴;总PIN数:4P;排数:1;每排PIN数:4;额定电流:3A;工作温度范围:-25°C~+85°C;")
      (fields
        (field (name "Manufacturer Part") "WAFER-XH2.54-4PLB")
        (field (name "Manufacturer") "XUNPU(讯普)")
      )
      (libsource (lib "easyedapro") (part "WAFER-XH2.54-4PLB"))
    )
    (comp (ref "CN15")
      (value "XH2.54-4PLT")
      (footprint "easyedapro:CONN-SMD_4P-P2.50_XUNPU_WAFER-XH2.54-4PLB")
      (description "插针结构:1x4P;间距:2.5mm;安装方式:立贴;总PIN数:4P;排数:1;每排PIN数:4;额定电流:3A;工作温度范围:-25°C~+85°C;")
      (fields
        (field (name "Manufacturer Part") "WAFER-XH2.54-4PLB")
        (field (name "Manufacturer") "XUNPU(讯普)")
      )
      (libsource (lib "easyedapro") (part "WAFER-XH2.54-4PLB"))
    )
    (comp (ref "CN16")
      (value "XH2.54-4PLT")
      (footprint "easyedapro:CONN-SMD_4P-P2.50_XUNPU_WAFER-XH2.54-4PLB")
      (description "插针结构:1x4P;间距:2.5mm;安装方式:立贴;总PIN数:4P;排数:1;每排PIN数:4;额定电流:3A;工作温度范围:-25°C~+85°C;")
      (fields (field (name "Manufacturer") "XUNPU(讯普)"))
      (libsource (lib "easyedapro") (part "WAFER-XH2.54-4PLB"))
    )
    (comp (ref "D4")
      (value "TPD1E05U06DPYR")
      (footprint "easyedapro:X2SON-2_L1.0-W0.6-P0.70-RD")
      (description "反向截止电压(Vrwm):5.5V@Max;最大钳位电压:14V;峰值脉冲电流(Ipp)@10/1000us:2.5A@8/20us;击穿电压:6V;")
      (fields (field (name "Manufacturer") "TI(德州仪器)"))
      (libsource (lib "easyedapro") (part "TPD1E05U06DPYR"))
    )
    (comp (ref "D5")
      (value "TPD1E05U06DPYR")
      (footprint "easyedapro:X2SON-2_L1.0-W0.6-P0.70-RD")
      (description "反向截止电压(Vrwm):5.5V@Max;最大钳位电压:14V;峰值脉冲电流(Ipp)@10/1000us:2.5A@8/20us;击穿电压:6V;")
      (fields (field (name "Manufacturer") "TI(德州仪器)"))
      (libsource (lib "easyedapro") (part "TPD1E05U06DPYR"))
    )
    (comp (ref "D6")
      (value "TPD1E05U06DPYR")
      (footprint "easyedapro:X2SON-2_L1.0-W0.6-P0.70-RD")
      (description "反向截止电压(Vrwm):5.5V@Max;最大钳位电压:14V;峰值脉冲电流(Ipp)@10/1000us:2.5A@8/20us;击穿电压:6V;")
      (fields (field (name "Manufacturer") "TI(德州仪器)"))
      (libsource (lib "easyedapro") (part "TPD1E05U06DPYR"))
    )
    (comp (ref "D7")
      (value "TPD1E05U06DPYR")
      (footprint "easyedapro:X2SON-2_L1.0-W0.6-P0.70-RD")
      (description "反向截止电压(Vrwm):5.5V@Max;最大钳位电压:14V;峰值脉冲电流(Ipp)@10/1000us:2.5A@8/20us;击穿电压:6V;")
      (fields (field (name "Manufacturer") "TI(德州仪器)"))
      (libsource (lib "easyedapro") (part "TPD1E05U06DPYR"))
    )
    (comp (ref "D8")
      (value "TPD1E05U06DPYR")
      (footprint "easyedapro:X2SON-2_L1.0-W0.6-P0.70-RD")
      (description "反向截止电压(Vrwm):5.5V@Max;最大钳位电压:14V;峰值脉冲电流(Ipp)@10/1000us:2.5A@8/20us;击穿电压:6V;")
      (fields (field (name "Manufacturer") "TI(德州仪器)"))
      (libsource (lib "easyedapro") (part "TPD1E05U06DPYR"))
    )
    (comp (ref "D9")
      (value "TPD1E05U06DPYR")
      (footprint "easyedapro:X2SON-2_L1.0-W0.6-P0.70-RD")
      (description "反向截止电压(Vrwm):5.5V@Max;最大钳位电压:14V;峰值脉冲电流(Ipp)@10/1000us:2.5A@8/20us;击穿电压:6V;")
      (fields (field (name "Manufacturer") "TI(德州仪器)"))
      (libsource (lib "easyedapro") (part "TPD1E05U06DPYR"))
    )
    (comp (ref "D10")
      (value "TPD1E05U06DPYR")
      (footprint "easyedapro:X2SON-2_L1.0-W0.6-P0.70-RD")
      (description "反向截止电压(Vrwm):5.5V@Max;最大钳位电压:14V;峰值脉冲电流(Ipp)@10/1000us:2.5A@8/20us;击穿电压:6V;")
      (fields (field (name "Manufacturer") "TI(德州仪器)"))
      (libsource (lib "easyedapro") (part "TPD1E05U06DPYR"))
    )
    (comp (ref "D11")
      (value "TPD1E05U06DPYR")
      (footprint "easyedapro:X2SON-2_L1.0-W0.6-P0.70-RD")
      (description "反向截止电压(Vrwm):5.5V@Max;最大钳位电压:14V;峰值脉冲电流(Ipp)@10/1000us:2.5A@8/20us;击穿电压:6V;")
      (fields (field (name "Manufacturer") "TI(德州仪器)"))
      (libsource (lib "easyedapro") (part "TPD1E05U06DPYR"))
    )
    (comp (ref "R15")
      (value "20Ω")
      (footprint "easyedapro:R0402")
      (description "电阻类型:厚膜电阻;阻值:22Ω;精度:±1%;功率:62.5mW;温度系数:±100ppm/°C;")
      (fields
        (field (name "Manufacturer Part") "0402WGF200JTCE")
        (field (name "Manufacturer") "UNI-ROYAL(厚声)")
        (field (name "Tolerance") "±1%")
      )
      (libsource (lib "easyedapro") (part "0402WGF220JTCE"))
    )
    (comp (ref "R16")
      (value "20Ω")
      (footprint "easyedapro:R0402")
      (description "电阻类型:厚膜电阻;阻值:22Ω;精度:±1%;功率:62.5mW;温度系数:±100ppm/°C;")
      (fields
        (field (name "Manufacturer Part") "0402WGF200JTCE")
        (field (name "Manufacturer") "UNI-ROYAL(厚声)")
        (field (name "Tolerance") "±1%")
      )
      (libsource (lib "easyedapro") (part "0402WGF220JTCE"))
    )
    (comp (ref "R17")
      (value "20Ω")
      (footprint "easyedapro:R0402")
      (description "电阻类型:厚膜电阻;阻值:22Ω;精度:±1%;功率:62.5mW;温度系数:±100ppm/°C;")
      (fields
        (field (name "Manufacturer Part") "0402WGF200JTCE")
        (field (name "Manufacturer") "UNI-ROYAL(厚声)")
        (field (name "Tolerance") "±1%")
      )
      (libsource (lib "easyedapro") (part "0402WGF220JTCE"))
    )
    (comp (ref "R18")
      (value "20Ω")
      (footprint "easyedapro:R0402")
      (description "电阻类型:厚膜电阻;阻值:22Ω;精度:±1%;功率:62.5mW;温度系数:±100ppm/°C;")
      (fields
        (field (name "Manufacturer Part") "0402WGF200JTCE")
        (field (name "Manufacturer") "UNI-ROYAL(厚声)")
        (field (name "Tolerance") "±1%")
      )
      (libsource (lib "easyedapro") (part "0402WGF220JTCE"))
    )
    (comp (ref "U3")
      (value "~")
      (footprint "easyedapro:ESP32-C3-SuperMini")
      (description "NoneName ESP32-C3-SuprMini Module")
      (libsource (lib "easyedapro") (part "ESP32-C3-SuperMini"))
    )
    (comp (ref "U4")
      (value "XL-1010RGBC-WS2812B")
      (footprint "easyedapro:LED-SMD_4P-L1.0-W1.0-TL_XL-1010RGBC-WS2812B")
      (fields (field (name "Manufacturer") "XINGLIGHT(成兴光)"))
      (libsource (lib "easyedapro") (part "XL-1010RGBC-WS2812B"))
    )
    (comp (ref "U5")
      (value "HC-JN254-2-04-Z")
      (footprint "easyedapro:IDC-TH_8P-P2.54-V-R2-C4-S2.54")
      (fields (field (name "Manufacturer") "HCTL(华灿天禄)"))
      (libsource (lib "easyedapro") (part "HC-JN254-2-04-Z"))
    )
    (comp (ref "U6")
      (value "XH2.54-6PLT")
      (footprint "easyedapro:COMM-SMD_6P-P2.50_SHOUHAN_2.54-6PLT")
      (description "插针结构:1x6P;间距:2.5mm;公母:公;安装方式:立贴;排数:1;每排PIN数:6;额定电流:3A;工作温度范围:-25°C~+105°C;")
      (fields (field (name "Manufacturer Part") "2.54-6PLT") (field (name "Manufacturer") "SHOU HAN(首韩)"))
      (libsource (lib "easyedapro") (part "2.54-6PLT"))
    )
  )
  (nets
    (net (code "1") (name "FDB0") (class "Default")
      (node (ref "C10") (pin "1") (pinfunction "1_1") (pintype "input"))
      (node (ref "R11") (pin "2") (pinfunction "2_2") (pintype "input"))
      (node (ref "R9") (pin "1") (pinfunction "1_1") (pintype "input"))
      (node (ref "U1") (pin "16") (pinfunction "VFB_16") (pintype "input"))
    )
    (net (code "2") (name "GND") (class "Default")
      (node (ref "C11") (pin "1") (pinfunction "1_1") (pintype "input"))
      (node (ref "C13") (pin "1") (pinfunction "1_1") (pintype "input"))
      (node (ref "C14") (pin "1") (pinfunction "1_1") (pintype "input"))
      (node (ref "C15") (pin "1") (pinfunction "1_1") (pintype "input"))
      (node (ref "C16") (pin "1") (pinfunction "1_1") (pintype "input"))
      (node (ref "C17") (pin "1") (pinfunction "1_1") (pintype "input"))
      (node (ref "C4") (pin "1") (pinfunction "1_1") (pintype "input"))
      (node (ref "C5") (pin "1") (pinfunction "1_1") (pintype "input"))
      (node (ref "C6") (pin "1") (pinfunction "1_1") (pintype "input"))
      (node (ref "C7") (pin "1") (pinfunction "1_1") (pintype "input"))
      (node (ref "C8") (pin "1") (pinfunction "1_1") (pintype "input"))
      (node (ref "C9") (pin "2") (pinfunction "2_2") (pintype "input"))
      (node (ref "CN10") (pin "3") (pinfunction "3_3") (pintype "unspecified"))
      (node (ref "CN10") (pin "4") (pinfunction "4_4") (pintype "unspecified"))
      (node (ref "CN11") (pin "3") (pinfunction "3_3") (pintype "unspecified"))
      (node (ref "CN11") (pin "4") (pinfunction "4_4") (pintype "unspecified"))
      (node (ref "CN12") (pin "3") (pinfunction "3_3") (pintype "unspecified"))
      (node (ref "CN12") (pin "4") (pinfunction "4_4") (pintype "unspecified"))
      (node (ref "CN13") (pin "3") (pinfunction "3_3") (pintype "unspecified"))
      (node (ref "CN13") (pin "4") (pinfunction "4_4") (pintype "unspecified"))
      (node (ref "CN14") (pin "4") (pinfunction "4_4") (pintype "unspecified"))
      (node (ref "CN14") (pin "5") (pinfunction "5_5") (pintype "unspecified"))
      (node (ref "CN14") (pin "6") (pinfunction "6_6") (pintype "unspecified"))
      (node (ref "CN15") (pin "4") (pinfunction "4_4") (pintype "unspecified"))
      (node (ref "CN15") (pin "5") (pinfunction "5_5") (pintype "unspecified"))
      (node (ref "CN15") (pin "6") (pinfunction "6_6") (pintype "unspecified"))
      (node (ref "CN16") (pin "2") (pinfunction "2_2") (pintype "unspecified"))
      (node (ref "CN16") (pin "5") (pinfunction "5_5") (pintype "unspecified"))
      (node (ref "CN16") (pin "6") (pinfunction "6_6") (pintype "unspecified"))
      (node (ref "CN8") (pin "3") (pinfunction "3_3") (pintype "unspecified"))
      (node (ref "CN8") (pin "4") (pinfunction "4_4") (pintype "unspecified"))
      (node (ref "CN9") (pin "3") (pinfunction "3_3") (pintype "unspecified"))
      (node (ref "CN9") (pin "4") (pinfunction "4_4") (pintype "unspecified"))
      (node (ref "D10") (pin "2") (pinfunction "GND_2") (pintype "unspecified"))
      (node (ref "D11") (pin "2") (pinfunction "GND_2") (pintype "unspecified"))
      (node (ref "D3") (pin "2") (pinfunction "A_2") (pintype "input"))
      (node (ref "D4") (pin "2") (pinfunction "GND_2") (pintype "unspecified"))
      (node (ref "D5") (pin "2") (pinfunction "GND_2") (pintype "unspecified"))
      (node (ref "D6") (pin "2") (pinfunction "GND_2") (pintype "unspecified"))
      (node (ref "D7") (pin "2") (pinfunction "GND_2") (pintype "unspecified"))
      (node (ref "D8") (pin "2") (pinfunction "GND_2") (pintype "unspecified"))
      (node (ref "D9") (pin "2") (pinfunction "GND_2") (pintype "unspecified"))
      (node (ref "H1") (pin "1") (pinfunction "1_1") (pintype "input"))
      (node (ref "H2") (pin "1") (pinfunction "1_1") (pintype "input"))
      (node (ref "H3") (pin "1") (pinfunction "1_1") (pintype "input"))
      (node (ref "H4") (pin "1") (pinfunction "1_1") (pintype "input"))
      (node (ref "Q2") (pin "1") (pinfunction "S1_1") (pintype "unspecified"))
      (node (ref "R11") (pin "1") (pinfunction "1_1") (pintype "input"))
      (node (ref "R12") (pin "1") (pinfunction "1_1") (pintype "input"))
      (node (ref "R13") (pin "1") (pinfunction "1_1") (pintype "input"))
      (node (ref "R14") (pin "1") (pinfunction "1_1") (pintype "input"))
      (node (ref "R7") (pin "1") (pinfunction "1_1") (pintype "input"))
      (node (ref "R8") (pin "2") (pinfunction "2_2") (pintype "input"))
      (node (ref "U1") (pin "1") (pinfunction "GND_1") (pintype "input"))
      (node (ref "U1") (pin "2") (pinfunction "GND_2") (pintype "input"))
      (node (ref "U1") (pin "21") (pinfunction "GND_21") (pintype "input"))
      (node (ref "U1") (pin "3") (pinfunction "GND_3") (pintype "input"))
      (node (ref "U3") (pin "10") (pinfunction "GND_10") (pintype "input"))
      (node (ref "U4") (pin "3") (pinfunction "GND_3") (pintype "unspecified"))
      (node (ref "U5") (pin "2") (pinfunction "2_2") (pintype "input"))
      (node (ref "U6") (pin "6") (pinfunction "6_6") (pintype "unspecified"))
      (node (ref "U6") (pin "7") (pinfunction "7_7") (pintype "unspecified"))
      (node (ref "U6") (pin "8") (pinfunction "8_8") (pintype "unspecified"))
      (node (ref "USB1") (pin "7") (pinfunction "EH_7") (pintype "unspecified"))
      (node (ref "USB1") (pin "A12") (pinfunction "GND_A12") (pintype "unspecified"))
      (node (ref "USB1") (pin "B12") (pinfunction "GND_B12") (pintype "unspecified"))
    )
    (net (code "3") (name "GND_BAT") (class "Default")
      (node (ref "CN1") (pin "1") (pinfunction "-_1") (pintype "unspecified"))
      (node (ref "CN2") (pin "2") (pinfunction "-_2") (pintype "unspecified"))
      (node (ref "CN3") (pin "2") (pinfunction "-_2") (pintype "unspecified"))
      (node (ref "CN4") (pin "2") (pinfunction "-_2") (pintype "unspecified"))
      (node (ref "CN5") (pin "2") (pinfunction "-_2") (pintype "unspecified"))
      (node (ref "CN6") (pin "2") (pinfunction "-_2") (pintype "unspecified"))
      (node (ref "CN7") (pin "2") (pinfunction "-_2") (pintype "unspecified"))
      (node (ref "D2") (pin "2") (pinfunction "A_2") (pintype "input"))
      (node (ref "Q2") (pin "7") (pinfunction "D1_7") (pintype "unspecified"))
      (node (ref "Q2") (pin "8") (pinfunction "D1_8") (pintype "unspecified"))
      (node (ref "R4") (pin "2") (pinfunction "2_2") (pintype "input"))
    )
    (net (code "4") (name "I2C2_SCL") (class "Default")
      (node (ref "CN14") (pin "2") (pinfunction "2_2") (pintype "unspecified"))
      (node (ref "U5") (pin "6") (pinfunction "6_6") (pintype "input"))
    )
    (net (code "5") (name "I2C2_SDA") (class "Default")
      (node (ref "CN14") (pin "3") (pinfunction "3_3") (pintype "unspecified"))
      (node (ref "U5") (pin "8") (pinfunction "8_8") (pintype "input"))
    )
    (net (code "6") (name "N_G") (class "Default")
      (node (ref "D3") (pin "1") (pinfunction "C_1") (pintype "input"))
      (node (ref "Q2") (pin "2") (pinfunction "G1_2") (pintype "unspecified"))
      (node (ref "R1") (pin "1") (pinfunction "1_1") (pintype "input"))
    )
    (net (code "7") (name "Net-(C1-Pad1)") (class "Default")
      (node (ref "C1") (pin "1") (pinfunction "1_1") (pintype "input"))
      (node (ref "R4") (pin "1") (pinfunction "1_1") (pintype "input"))
    )
    (net (code "8") (name "Net-(C3-Pad1)") (class "Default")
      (node (ref "C3") (pin "1") (pinfunction "1_1") (pintype "input"))
      (node (ref "R6") (pin "2") (pinfunction "2_2") (pintype "input"))
    )
    (net (code "9") (name "Net-(C12-Pad1)") (class "Default")
      (node (ref "C12") (pin "1") (pinfunction "1_1") (pintype "input"))
      (node (ref "R10") (pin "2") (pinfunction "2_2") (pintype "input"))
    )
    (net (code "10") (name "Net-(CN10-Pad1)") (class "Default")
      (node (ref "CN10") (pin "1") (pinfunction "1_1") (pintype "unspecified"))
      (node (ref "CN11") (pin "1") (pinfunction "1_1") (pintype "unspecified"))
      (node (ref "CN12") (pin "1") (pinfunction "1_1") (pintype "unspecified"))
      (node (ref "CN13") (pin "1") (pinfunction "1_1") (pintype "unspecified"))
      (node (ref "CN8") (pin "1") (pinfunction "1_1") (pintype "unspecified"))
      (node (ref "CN9") (pin "1") (pinfunction "1_1") (pintype "unspecified"))
    )
    (net (code "11") (name "Net-(CN10-Pad2)") (class "Default")
      (node (ref "CN10") (pin "2") (pinfunction "2_2") (pintype "unspecified"))
      (node (ref "CN11") (pin "2") (pinfunction "2_2") (pintype "unspecified"))
      (node (ref "CN12") (pin "2") (pinfunction "2_2") (pintype "unspecified"))
      (node (ref "CN13") (pin "2") (pinfunction "2_2") (pintype "unspecified"))
      (node (ref "CN8") (pin "2") (pinfunction "2_2") (pintype "unspecified"))
      (node (ref "CN9") (pin "2") (pinfunction "2_2") (pintype "unspecified"))
    )
    (net (code "12") (name "Net-(D1-A)") (class "Default")
      (node (ref "C2") (pin "2") (pinfunction "2_2") (pintype "input"))
      (node (ref "C3") (pin "2") (pinfunction "2_2") (pintype "input"))
      (node (ref "D1") (pin "2") (pinfunction "A_2") (pintype "input"))
      (node (ref "Q1") (pin "3") (pinfunction "C_3") (pintype "input"))
      (node (ref "R3") (pin "2") (pinfunction "2_2") (pintype "input"))
      (node (ref "R7") (pin "2") (pinfunction "2_2") (pintype "input"))
    )
    (net (code "13") (name "Net-(D2-C)") (class "Default")
      (node (ref "D2") (pin "1") (pinfunction "C_1") (pintype "input"))
      (node (ref "R2") (pin "2") (pinfunction "2_2") (pintype "input"))
      (node (ref "R5") (pin "2") (pinfunction "2_2") (pintype "input"))
    )
    (net (code "14") (name "Net-(LED1--)") (class "Default")
      (node (ref "LED1") (pin "2") (pinfunction "-_2") (pintype "unspecified"))
      (node (ref "R14") (pin "2") (pinfunction "2_2") (pintype "input"))
    )
    (net (code "15") (name "Net-(Q1-B)") (class "Default")
      (node (ref "Q1") (pin "1") (pinfunction "B_1") (pintype "input"))
      (node (ref "R5") (pin "1") (pinfunction "1_1") (pintype "input"))
    )
    (net (code "16") (name "Net-(Q3-G)") (class "Default")
      (node (ref "Q3") (pin "4") (pinfunction "G_4") (pintype "input"))
      (node (ref "Q4") (pin "3") (pinfunction "C2_3") (pintype "input"))
      (node (ref "R13") (pin "2") (pinfunction "2_2") (pintype "input"))
    )
    (net (code "17") (name "Net-(Q4-B1)") (class "Default")
      (node (ref "Q4") (pin "2") (pinfunction "B1_2") (pintype "input"))
      (node (ref "Q4") (pin "5") (pinfunction "B2_5") (pintype "input"))
      (node (ref "Q4") (pin "6") (pinfunction "C1_6") (pintype "input"))
      (node (ref "R12") (pin "2") (pinfunction "2_2") (pintype "input"))
    )
    (net (code "18") (name "Net-(Q4-E1)") (class "Default")
      (node (ref "Q3") (pin "5") (pinfunction "D_5") (pintype "input"))
      (node (ref "Q3") (pin "6") (pinfunction "D_6") (pintype "input"))
      (node (ref "Q3") (pin "7") (pinfunction "D_7") (pintype "input"))
      (node (ref "Q3") (pin "8") (pinfunction "D_8") (pintype "input"))
      (node (ref "Q3") (pin "9") (pinfunction "D_9") (pintype "input"))
      (node (ref "Q4") (pin "1") (pinfunction "E1_1") (pintype "input"))
      (node (ref "U1") (pin "18") (pinfunction "CSN1_18") (pintype "input"))
      (node (ref "U1") (pin "19") (pinfunction "CSN2_19") (pintype "input"))
      (node (ref "U2") (pin "2") (pinfunction "2_2") (pintype "unspecified"))
    )
    (net (code "19") (name "Net-(U1-BST)") (class "Default")
      (node (ref "R10") (pin "1") (pinfunction "1_1") (pintype "input"))
      (node (ref "U1") (pin "10") (pinfunction "BST_10") (pintype "input"))
    )
    (net (code "20") (name "Net-(U1-CSP)") (class "Default")
      (node (ref "C10") (pin "2") (pinfunction "2_2") (pintype "input"))
      (node (ref "C7") (pin "2") (pinfunction "2_2") (pintype "input"))
      (node (ref "C8") (pin "2") (pinfunction "2_2") (pintype "input"))
      (node (ref "C9") (pin "1") (pinfunction "1_1") (pintype "input"))
      (node (ref "L1") (pin "2") (pinfunction "2_2") (pintype "input"))
      (node (ref "R9") (pin "2") (pinfunction "2_2") (pintype "input"))
      (node (ref "U1") (pin "17") (pinfunction "CSP_17") (pintype "input"))
      (node (ref "U2") (pin "1") (pinfunction "1_1") (pintype "unspecified"))
    )
    (net (code "21") (name "Net-(U1-FS)") (class "Default")
      (node (ref "R8") (pin "1") (pinfunction "1_1") (pintype "input"))
      (node (ref "U1") (pin "20") (pinfunction "FS_20") (pintype "input"))
    )
    (net (code "22") (name "PIN0") (class "Default")
      (node (ref "D4") (pin "1") (pinfunction "I/O_1") (pintype "unspecified"))
      (node (ref "U3") (pin "16") (pinfunction "Pin0_16") (pintype "input"))
      (node (ref "U6") (pin "2") (pinfunction "2_2") (pintype "unspecified"))
    )
    (net (code "23") (name "PIN1") (class "Default")
      (node (ref "D5") (pin "1") (pinfunction "I/O_1") (pintype "unspecified"))
      (node (ref "U3") (pin "15") (pinfunction "Pin1_15") (pintype "input"))
      (node (ref "U6") (pin "3") (pinfunction "3_3") (pintype "unspecified"))
    )
    (net (code "24") (name "PIN2") (class "Default")
      (node (ref "D6") (pin "1") (pinfunction "I/O_1") (pintype "unspecified"))
      (node (ref "U3") (pin "14") (pinfunction "Pin2_14") (pintype "input"))
      (node (ref "U6") (pin "4") (pinfunction "4_4") (pintype "unspecified"))
    )
    (net (code "25") (name "PIN3") (class "Default")
      (node (ref "D7") (pin "1") (pinfunction "I/O_1") (pintype "unspecified"))
      (node (ref "U3") (pin "13") (pinfunction "Pin3_13") (pintype "input"))
      (node (ref "U6") (pin "5") (pinfunction "5_5") (pintype "unspecified"))
    )
    (net (code "26") (name "PIN4") (class "Default")
      (node (ref "R16") (pin "2") (pinfunction "2_2") (pintype "input"))
      (node (ref "U3") (pin "12") (pinfunction "Pin4_12") (pintype "input"))
    )
    (net (code "27") (name "PIN5") (class "Default")
      (node (ref "R18") (pin "2") (pinfunction "2_2") (pintype "input"))
      (node (ref "U3") (pin "1") (pinfunction "Pin5_1") (pintype "input"))
    )
    (net (code "28") (name "PIN6") (class "Default")
      (node (ref "R17") (pin "2") (pinfunction "2_2") (pintype "input"))
      (node (ref "U3") (pin "2") (pinfunction "Pin6_2") (pintype "input"))
    )
    (net (code "29") (name "PIN7") (class "Default")
      (node (ref "R15") (pin "2") (pinfunction "2_2") (pintype "input"))
      (node (ref "U3") (pin "3") (pinfunction "Pin7_3") (pintype "input"))
    )
    (net (code "30") (name "PIN8") (class "Default")
      (node (ref "CN15") (pin "2") (pinfunction "2_2") (pintype "unspecified"))
      (node (ref "D8") (pin "1") (pinfunction "I/O_1") (pintype "unspecified"))
      (node (ref "U3") (pin "4") (pinfunction "Pin8_4") (pintype "input"))
    )
    (net (code "31") (name "PIN9") (class "Default")
      (node (ref "CN15") (pin "3") (pinfunction "3_3") (pintype "unspecified"))
      (node (ref "D9") (pin "1") (pinfunction "I/O_1") (pintype "unspecified"))
      (node (ref "U3") (pin "5") (pinfunction "Pin9_5") (pintype "input"))
    )
    (net (code "32") (name "PIN10") (class "Default")
      (node (ref "U3") (pin "6") (pinfunction "Pin10_6") (pintype "input"))
      (node (ref "U4") (pin "4") (pinfunction "DIN_4") (pintype "unspecified"))
    )
    (net (code "33") (name "PIN20") (class "Default")
      (node (ref "CN16") (pin "3") (pinfunction "3_3") (pintype "unspecified"))
      (node (ref "D10") (pin "1") (pinfunction "I/O_1") (pintype "unspecified"))
      (node (ref "U3") (pin "7") (pinfunction "Pin20_7") (pintype "input"))
    )
    (net (code "34") (name "PIN21") (class "Default")
      (node (ref "CN16") (pin "4") (pinfunction "4_4") (pintype "unspecified"))
      (node (ref "D11") (pin "1") (pinfunction "I/O_1") (pintype "unspecified"))
      (node (ref "U3") (pin "8") (pinfunction "Pin21_8") (pintype "input"))
    )
    (net (code "35") (name "P_G") (class "Default")
      (node (ref "Q2") (pin "4") (pinfunction "G2_4") (pintype "unspecified"))
      (node (ref "R3") (pin "1") (pinfunction "1_1") (pintype "input"))
    )
    (net (code "36") (name "SPI2_CLK") (class "Default")
      (node (ref "R16") (pin "1") (pinfunction "1_1") (pintype "input"))
      (node (ref "U5") (pin "3") (pinfunction "3_3") (pintype "input"))
    )
    (net (code "37") (name "SPI2_CS") (class "Default")
      (node (ref "R15") (pin "1") (pinfunction "1_1") (pintype "input"))
      (node (ref "U5") (pin "1") (pinfunction "1_1") (pintype "input"))
    )
    (net (code "38") (name "SPI2_MISO") (class "Default")
      (node (ref "R18") (pin "1") (pinfunction "1_1") (pintype "input"))
      (node (ref "U5") (pin "7") (pinfunction "7_7") (pintype "input"))
    )
    (net (code "39") (name "SPI2_MOSI") (class "Default")
      (node (ref "R17") (pin "1") (pinfunction "1_1") (pintype "input"))
      (node (ref "U5") (pin "5") (pinfunction "5_5") (pintype "input"))
    )
    (net (code "40") (name "SW") (class "Default")
      (node (ref "C12") (pin "2") (pinfunction "2_2") (pintype "input"))
      (node (ref "L1") (pin "1") (pinfunction "1_1") (pintype "input"))
      (node (ref "U1") (pin "12") (pinfunction "SW_12") (pintype "input"))
      (node (ref "U1") (pin "13") (pinfunction "SW_13") (pintype "input"))
      (node (ref "U1") (pin "14") (pinfunction "SW_14") (pintype "input"))
      (node (ref "U1") (pin "23") (pinfunction "SW_23") (pintype "input"))
    )
    (net (code "41") (name "VCC_5V") (class "Default")
      (node (ref "C11") (pin "2") (pinfunction "2_2") (pintype "input"))
      (node (ref "C13") (pin "2") (pinfunction "2_2") (pintype "input"))
      (node (ref "C14") (pin "2") (pinfunction "2_2") (pintype "input"))
      (node (ref "C15") (pin "2") (pinfunction "2_2") (pintype "input"))
      (node (ref "C16") (pin "2") (pinfunction "2_2") (pintype "input"))
      (node (ref "C17") (pin "2") (pinfunction "2_2") (pintype "input"))
      (node (ref "CN14") (pin "1") (pinfunction "1_1") (pintype "unspecified"))
      (node (ref "CN15") (pin "1") (pinfunction "1_1") (pintype "unspecified"))
      (node (ref "CN16") (pin "1") (pinfunction "1_1") (pintype "unspecified"))
      (node (ref "LED1") (pin "1") (pinfunction "+_1") (pintype "unspecified"))
      (node (ref "Q3") (pin "0") (pinfunction "S_0") (pintype "input"))
      (node (ref "Q3") (pin "1") (pinfunction "S_1") (pintype "input"))
      (node (ref "Q3") (pin "2") (pinfunction "S_2") (pintype "input"))
      (node (ref "Q3") (pin "3") (pinfunction "S_3") (pintype "input"))
      (node (ref "Q4") (pin "4") (pinfunction "E2_4") (pintype "input"))
      (node (ref "U3") (pin "9") (pinfunction "5V_9") (pintype "input"))
      (node (ref "U4") (pin "2") (pinfunction "VDD_2") (pintype "unspecified"))
      (node (ref "U6") (pin "1") (pinfunction "1_1") (pintype "unspecified"))
      (node (ref "USB1") (pin "A9") (pinfunction "VBUS_A9") (pintype "unspecified"))
      (node (ref "USB1") (pin "B9") (pinfunction "VBUS_B9") (pintype "unspecified"))
    )
    (net (code "42") (name "VCC_BAT") (class "Default")
      (node (ref "C1") (pin "2") (pinfunction "2_2") (pintype "input"))
      (node (ref "C2") (pin "1") (pinfunction "1_1") (pintype "input"))
      (node (ref "CN1") (pin "2") (pinfunction "+_2") (pintype "unspecified"))
      (node (ref "CN2") (pin "1") (pinfunction "+_1") (pintype "unspecified"))
      (node (ref "CN3") (pin "1") (pinfunction "+_1") (pintype "unspecified"))
      (node (ref "CN4") (pin "1") (pinfunction "+_1") (pintype "unspecified"))
      (node (ref "CN5") (pin "1") (pinfunction "+_1") (pintype "unspecified"))
      (node (ref "CN6") (pin "1") (pinfunction "+_1") (pintype "unspecified"))
      (node (ref "CN7") (pin "1") (pinfunction "+_1") (pintype "unspecified"))
      (node (ref "D1") (pin "1") (pinfunction "C_1") (pintype "input"))
      (node (ref "Q1") (pin "2") (pinfunction "E_2") (pintype "input"))
      (node (ref "Q2") (pin "3") (pinfunction "S2_3") (pintype "unspecified"))
      (node (ref "R1") (pin "2") (pinfunction "2_2") (pintype "input"))
      (node (ref "R2") (pin "1") (pinfunction "1_1") (pintype "input"))
    )
    (net (code "43") (name "VCC_IN") (class "Default")
      (node (ref "C4") (pin "2") (pinfunction "2_2") (pintype "input"))
      (node (ref "C5") (pin "2") (pinfunction "2_2") (pintype "input"))
      (node (ref "C6") (pin "2") (pinfunction "2_2") (pintype "input"))
      (node (ref "Q2") (pin "5") (pinfunction "D2_5") (pintype "unspecified"))
      (node (ref "Q2") (pin "6") (pinfunction "D2_6") (pintype "unspecified"))
      (node (ref "R6") (pin "1") (pinfunction "1_1") (pintype "input"))
      (node (ref "U1") (pin "22") (pinfunction "VIN_22") (pintype "input"))
      (node (ref "U1") (pin "6") (pinfunction "VIN_6") (pintype "input"))
      (node (ref "U1") (pin "7") (pinfunction "VIN_7") (pintype "input"))
      (node (ref "U1") (pin "8") (pinfunction "VIN_8") (pintype "input"))
    )
    (net (code "44") (name "unconnected-(CN1-Pad3)") (class "Default")
      (node (ref "CN1") (pin "3") (pinfunction "3_3") (pintype "unspecified+no_connect"))
    )
    (net (code "45") (name "unconnected-(CN1-Pad4)") (class "Default")
      (node (ref "CN1") (pin "4") (pinfunction "4_4") (pintype "unspecified+no_connect"))
    )
    (net (code "46") (name "unconnected-(U1-NC-Pad4)") (class "Default")
      (node (ref "U1") (pin "4") (pinfunction "NC_4") (pintype "input+no_connect"))
    )
    (net (code "47") (name "unconnected-(U1-NC-Pad5)") (class "Default")
      (node (ref "U1") (pin "5") (pinfunction "NC_5") (pintype "input+no_connect"))
    )
    (net (code "48") (name "unconnected-(U1-NC-Pad9)") (class "Default")
      (node (ref "U1") (pin "9") (pinfunction "NC_9") (pintype "input+no_connect"))
    )
    (net (code "49") (name "unconnected-(U1-NC-Pad11)") (class "Default")
      (node (ref "U1") (pin "11") (pinfunction "NC_11") (pintype "input+no_connect"))
    )
    (net (code "50") (name "unconnected-(U1-NC-Pad15)") (class "Default")
      (node (ref "U1") (pin "15") (pinfunction "NC_15") (pintype "input+no_connect"))
    )
    (net (code "51") (name "unconnected-(U3-3V3-Pad11)") (class "Default")
      (node (ref "U3") (pin "11") (pinfunction "3V3_11") (pintype "input+no_connect"))
    )
    (net (code "52") (name "unconnected-(U4-DOUT-Pad1)") (class "Default")
      (node (ref "U4") (pin "1") (pinfunction "DOUT_1") (pintype "unspecified+no_connect"))
    )
    (net (code "53") (name "unconnected-(U5-Pad4)") (class "Default")
      (node (ref "U5") (pin "4") (pinfunction "4_4") (pintype "input+no_connect"))
    )
    (net (code "54") (name "unconnected-(USB1-CC1-PadA5)") (class "Default")
      (node (ref "USB1") (pin "A5") (pinfunction "CC1_A5") (pintype "unspecified+no_connect"))
    )
    (net (code "55") (name "unconnected-(USB1-CC2-PadB5)") (class "Default")
      (node (ref "USB1") (pin "B5") (pinfunction "CC2_B5") (pintype "unspecified+no_connect"))
    )
  )
)
